# power_NAND_2input.net
KiCad netlist of a schematic drawn in EAGLE
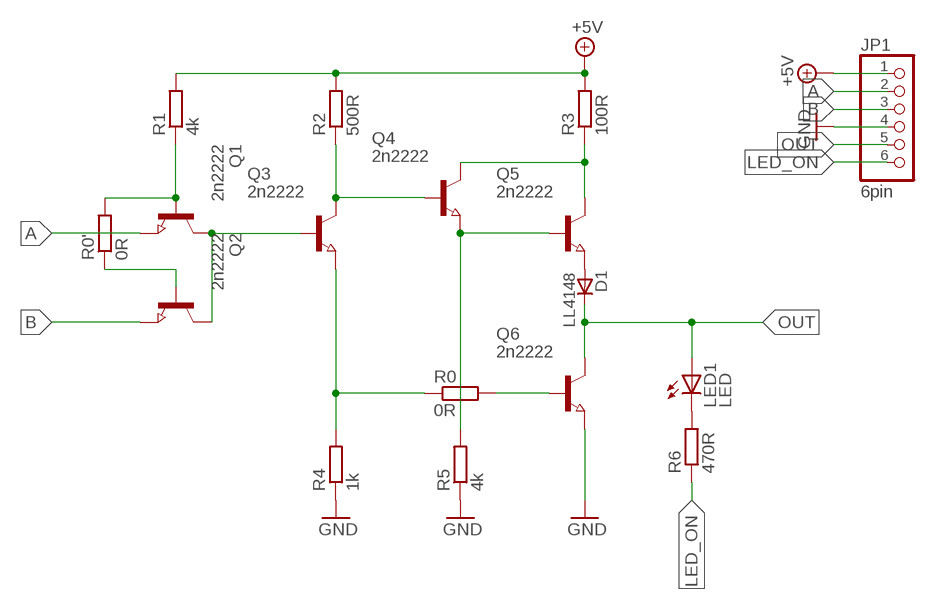
[diagram p0: schematic, sheet 1]

(export (version "E")
  (design (tool "Eeschema 10.0.6"))
  (components
    (comp (ref "D1")
      (value "LL4148")
      (footprint "eagle-import:SOD80_DO213AA_MINIMELF")
      (libsource (lib "eagle-import") (part "LL4148"))
    )
    (comp (ref "JP1")
      (value "6pin")
      (footprint "eagle-import:1X06SMD_90")
      (libsource (lib "eagle-import") (part "PINHD-1X06_2.54-SMD-90°"))
    )
    (comp (ref "LED1")
      (value "LED")
      (footprint "eagle-import:CHIPLED_0805")
      (libsource (lib "eagle-import") (part "LEDCHIPLED_0805"))
    )
    (comp (ref "Q1")
      (value "2n2222")
      (footprint "eagle-import:SOT23")
      (libsource (lib "eagle-import") (part "NPN-TRANSISTOR_SOT23"))
    )
    (comp (ref "Q2")
      (value "2n2222")
      (footprint "eagle-import:SOT23")
      (libsource (lib "eagle-import") (part "NPN-TRANSISTOR_SOT23"))
    )
    (comp (ref "Q3")
      (value "2n2222")
      (footprint "eagle-import:SOT23")
      (libsource (lib "eagle-import") (part "NPN-TRANSISTOR_SOT23"))
    )
    (comp (ref "Q4")
      (value "2n2222")
      (footprint "eagle-import:SOT23")
      (libsource (lib "eagle-import") (part "NPN-TRANSISTOR_SOT23"))
    )
    (comp (ref "Q5")
      (value "2n2222")
      (footprint "eagle-import:SOT23")
      (libsource (lib "eagle-import") (part "NPN-TRANSISTOR_SOT23"))
    )
    (comp (ref "Q6")
      (value "2n2222")
      (footprint "eagle-import:SOT23")
      (libsource (lib "eagle-import") (part "NPN-TRANSISTOR_SOT23"))
    )
    (comp (ref "R0")
      (value "0R")
      (footprint "eagle-import:R1206")
      (libsource (lib "eagle-import") (part "R-EU_R1206"))
    )
    (comp (ref "R0'")
      (value "0R")
      (footprint "eagle-import:R1206")
      (libsource (lib "eagle-import") (part "R-EU_R1206"))
    )
    (comp (ref "R1")
      (value "4k")
      (footprint "eagle-import:R0805")
      (libsource (lib "eagle-import") (part "R-EU_R0805"))
    )
    (comp (ref "R2")
      (value "500R")
      (footprint "eagle-import:R0805")
      (libsource (lib "eagle-import") (part "R-EU_R0805"))
    )
    (comp (ref "R3")
      (value "100R")
      (footprint "eagle-import:R0805")
      (libsource (lib "eagle-import") (part "R-EU_R0805"))
    )
    (comp (ref "R4")
      (value "1k")
      (footprint "eagle-import:R0805")
      (libsource (lib "eagle-import") (part "R-EU_R0805"))
    )
    (comp (ref "R5")
      (value "4k")
      (footprint "eagle-import:R0805")
      (libsource (lib "eagle-import") (part "R-EU_R0805"))
    )
    (comp (ref "R6")
      (value "470R")
      (footprint "eagle-import:R0805")
      (libsource (lib "eagle-import") (part "R-EU_R0805"))
    )
  )
  (nets
    (net (code "1") (name "+5V") (class "Default")
      (node (ref "JP1") (pin "1") (pinfunction "1_1") (pintype "passive"))
      (node (ref "R1") (pin "2") (pinfunction "2_2") (pintype "passive"))
      (node (ref "R2") (pin "2") (pinfunction "2_2") (pintype "passive"))
      (node (ref "R3") (pin "2") (pinfunction "2_2") (pintype "passive"))
    )
    (net (code "2") (name "A") (class "Default")
      (node (ref "JP1") (pin "2") (pinfunction "2_2") (pintype "passive"))
      (node (ref "Q1") (pin "2") (pinfunction "E_2") (pintype "passive"))
    )
    (net (code "3") (name "B") (class "Default")
      (node (ref "JP1") (pin "3") (pinfunction "3_3") (pintype "passive"))
      (node (ref "Q2") (pin "2") (pinfunction "E_2") (pintype "passive"))
    )
    (net (code "4") (name "GND") (class "Default")
      (node (ref "JP1") (pin "4") (pinfunction "4_4") (pintype "passive"))
      (node (ref "Q6") (pin "2") (pinfunction "E_2") (pintype "passive"))
      (node (ref "R4") (pin "1") (pinfunction "1_1") (pintype "passive"))
      (node (ref "R5") (pin "1") (pinfunction "1_1") (pintype "passive"))
    )
    (net (code "5") (name "LED_ON") (class "Default")
      (node (ref "JP1") (pin "6") (pinfunction "6_6") (pintype "passive"))
      (node (ref "R6") (pin "1") (pinfunction "1_1") (pintype "passive"))
    )
    (net (code "6") (name "Net-(LED1-PadC)") (class "Default")
      (node (ref "LED1") (pin "C") (pinfunction "C_C") (pintype "passive"))
      (node (ref "R6") (pin "2") (pinfunction "2_2") (pintype "passive"))
    )
    (net (code "7") (name "Net-(Q1-B)") (class "Default")
      (node (ref "Q1") (pin "1") (pinfunction "B_1") (pintype "passive"))
      (node (ref "R0'") (pin "2") (pinfunction "2_2") (pintype "passive"))
      (node (ref "R1") (pin "1") (pinfunction "1_1") (pintype "passive"))
    )
    (net (code "8") (name "Net-(Q1-C)") (class "Default")
      (node (ref "Q1") (pin "3") (pinfunction "C_3") (pintype "passive"))
      (node (ref "Q2") (pin "3") (pinfunction "C_3") (pintype "passive"))
      (node (ref "Q3") (pin "1") (pinfunction "B_1") (pintype "passive"))
    )
    (net (code "9") (name "Net-(Q2-B)") (class "Default")
      (node (ref "Q2") (pin "1") (pinfunction "B_1") (pintype "passive"))
      (node (ref "R0'") (pin "1") (pinfunction "1_1") (pintype "passive"))
    )
    (net (code "10") (name "Net-(Q3-C)") (class "Default")
      (node (ref "Q3") (pin "3") (pinfunction "C_3") (pintype "passive"))
      (node (ref "Q4") (pin "1") (pinfunction "B_1") (pintype "passive"))
      (node (ref "R2") (pin "1") (pinfunction "1_1") (pintype "passive"))
    )
    (net (code "11") (name "Net-(Q3-E)") (class "Default")
      (node (ref "Q3") (pin "2") (pinfunction "E_2") (pintype "passive"))
      (node (ref "R0") (pin "1") (pinfunction "1_1") (pintype "passive"))
      (node (ref "R4") (pin "2") (pinfunction "2_2") (pintype "passive"))
    )
    (net (code "12") (name "Net-(Q4-C)") (class "Default")
      (node (ref "Q4") (pin "3") (pinfunction "C_3") (pintype "passive"))
      (node (ref "Q5") (pin "3") (pinfunction "C_3") (pintype "passive"))
      (node (ref "R3") (pin "1") (pinfunction "1_1") (pintype "passive"))
    )
    (net (code "13") (name "Net-(Q4-E)") (class "Default")
      (node (ref "Q4") (pin "2") (pinfunction "E_2") (pintype "passive"))
      (node (ref "Q5") (pin "1") (pinfunction "B_1") (pintype "passive"))
      (node (ref "R5") (pin "2") (pinfunction "2_2") (pintype "passive"))
    )
    (net (code "14") (name "Net-(Q5-E)") (class "Default")
      (node (ref "D1") (pin "A") (pinfunction "A_A") (pintype "passive"))
      (node (ref "Q5") (pin "2") (pinfunction "E_2") (pintype "passive"))
    )
    (net (code "15") (name "Net-(Q6-B)") (class "Default")
      (node (ref "Q6") (pin "1") (pinfunction "B_1") (pintype "passive"))
      (node (ref "R0") (pin "2") (pinfunction "2_2") (pintype "passive"))
    )
    (net (code "16") (name "OUT") (class "Default")
      (node (ref "D1") (pin "C") (pinfunction "C_C") (pintype "passive"))
      (node (ref "JP1") (pin "5") (pinfunction "5_5") (pintype "passive"))
      (node (ref "LED1") (pin "A") (pinfunction "A_A") (pintype "passive"))
      (node (ref "Q6") (pin "3") (pinfunction "C_3") (pintype "passive"))
    )
  )
)
